# power.net
KiCad netlist of a schematic drawn in Altium Designer
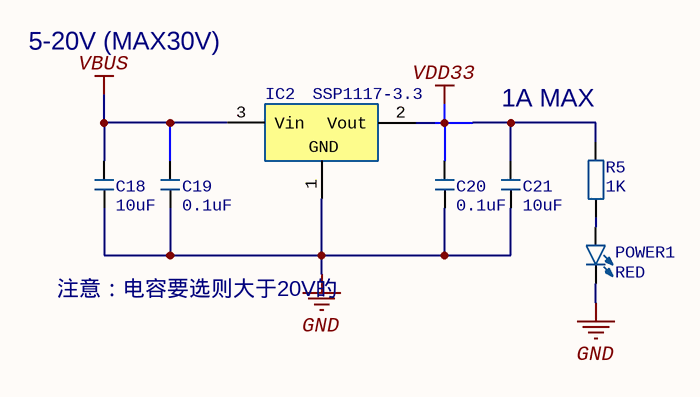
[diagram p0: power.SchDoc]

(export (version "E")
  (design (tool "Eeschema 10.0.6"))
  (components
    (comp (ref "C18")
      (value "10uF")
      (footprint "C 0603_L")
      (description "无极性贴片电容")
      (fields (field (name "版权归属") "源创客"))
      (libsource (lib "SCH-电阻-电容-电感") (part "C"))
    )
    (comp (ref "C19")
      (value "0.1uF")
      (footprint "C 0603_L")
      (description "无极性贴片电容")
      (fields (field (name "版权归属") "源创客"))
      (libsource (lib "SCH-电阻-电容-电感") (part "C"))
    )
    (comp (ref "C20")
      (value "0.1uF")
      (footprint "C 0603_L")
      (description "无极性贴片电容")
      (fields (field (name "版权归属") "源创客"))
      (libsource (lib "SCH-电阻-电容-电感") (part "C"))
    )
    (comp (ref "C21")
      (value "10uF")
      (footprint "C 0603_L")
      (description "无极性贴片电容")
      (fields (field (name "版权归属") "源创客"))
      (libsource (lib "SCH-电阻-电容-电感") (part "C"))
    )
    (comp (ref "IC2")
      (value "SSP1117-3.3")
      (footprint "SOT223_N")
      (description "LDO 3.3V  1A  压差1.3V （x~20V  极限30V）")
      (libsource (lib "SCH-电源类芯片") (part "SSP1117-3.3"))
    )
    (comp (ref "POWER1")
      (value "RED")
      (footprint "LED 0603R")
      (description "贴片LED")
      (fields (field (name "版权归属") "源创客"))
      (libsource (lib "SCH-LED") (part "LED-SMD"))
    )
    (comp (ref "R5")
      (value "1K")
      (footprint "R 0603_L")
      (description "贴片电阻")
      (fields (field (name "版权归属") "源创客"))
      (libsource (lib "SCH-电阻-电容-电感") (part "R"))
    )
  )
  (nets
    (net (code "1") (name "GND") (class "Default")
      (node (ref "C18") (pin "1") (pinfunction "1_1") (pintype "passive"))
      (node (ref "C19") (pin "1") (pinfunction "1_1") (pintype "passive"))
      (node (ref "C20") (pin "1") (pinfunction "1_1") (pintype "passive"))
      (node (ref "C21") (pin "1") (pinfunction "1_1") (pintype "passive"))
      (node (ref "IC2") (pin "1") (pinfunction "GND_1") (pintype "passive"))
      (node (ref "POWER1") (pin "2") (pinfunction "K_2") (pintype "passive"))
    )
    (net (code "2") (name "Net-(POWER1-A)") (class "Default")
      (node (ref "POWER1") (pin "1") (pinfunction "A_1") (pintype "passive"))
      (node (ref "R5") (pin "1") (pinfunction "1_1") (pintype "passive"))
    )
    (net (code "3") (name "VBUS") (class "Default")
      (node (ref "C18") (pin "2") (pinfunction "2_2") (pintype "passive"))
      (node (ref "C19") (pin "2") (pinfunction "2_2") (pintype "passive"))
      (node (ref "IC2") (pin "3") (pinfunction "Vin_3") (pintype "passive"))
    )
    (net (code "4") (name "VDD33") (class "Default")
      (node (ref "C20") (pin "2") (pinfunction "2_2") (pintype "passive"))
      (node (ref "C21") (pin "2") (pinfunction "2_2") (pintype "passive"))
      (node (ref "IC2") (pin "2") (pinfunction "Vout_2") (pintype "passive"))
      (node (ref "R5") (pin "2") (pinfunction "2_2") (pintype "passive"))
    )
  )
)
